# EC_isolated_SMD.net
KiCad netlist of a schematic drawn in EAGLE
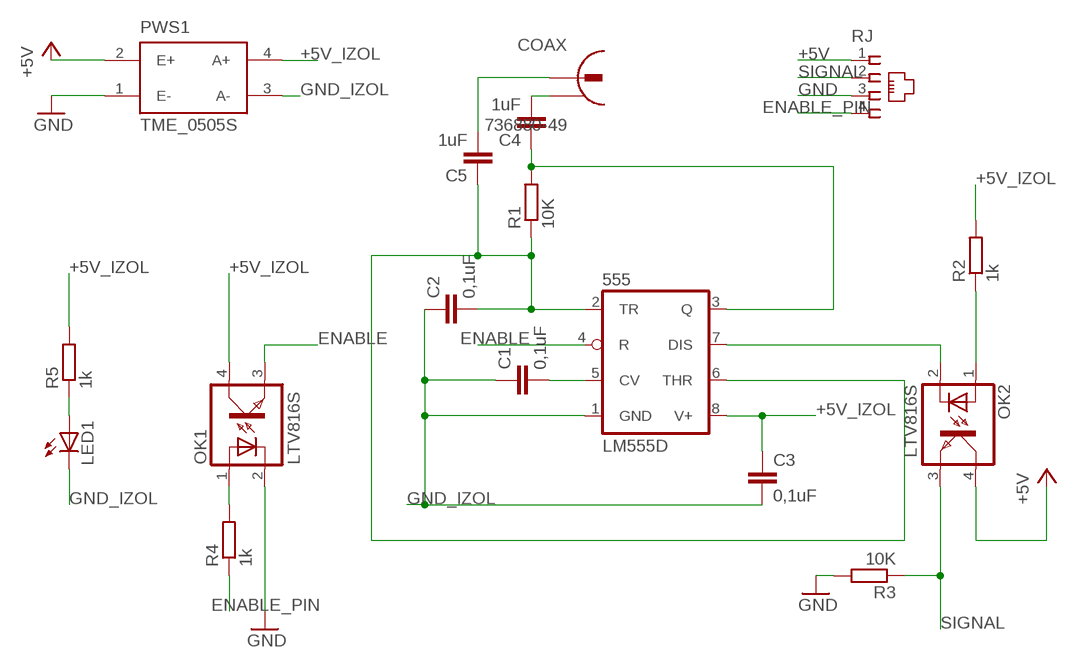
[diagram p0: schematic, sheet 1]

(export (version "E")
  (design (tool "Eeschema 10.0.6"))
  (components
    (comp (ref "555")
      (value "LM555D")
      (footprint "eagle-import:SO08")
      (libsource (lib "eagle-import") (part "555DLM"))
    )
    (comp (ref "C1")
      (value "0,1uF")
      (footprint "eagle-import:C1206")
      (libsource (lib "eagle-import") (part "C-EUC1206"))
    )
    (comp (ref "C2")
      (value "0,1uF")
      (footprint "eagle-import:C1206")
      (libsource (lib "eagle-import") (part "C-EUC1206"))
    )
    (comp (ref "C3")
      (value "0,1uF")
      (footprint "eagle-import:C1206")
      (libsource (lib "eagle-import") (part "C-EUC1206"))
    )
    (comp (ref "C4")
      (value "1uF")
      (footprint "eagle-import:C1206")
      (libsource (lib "eagle-import") (part "C-EUC1206"))
    )
    (comp (ref "C5")
      (value "1uF")
      (footprint "eagle-import:C1206")
      (libsource (lib "eagle-import") (part "C-EUC1206"))
    )
    (comp (ref "COAX")
      (value "736880-49")
      (footprint "eagle-import:736880-49")
      (libsource (lib "eagle-import") (part "736880-49"))
    )
    (comp (ref "LED1")
      (value "LEDLZR181")
      (footprint "eagle-import:LZR181")
      (libsource (lib "eagle-import") (part "LEDLZR181"))
    )
    (comp (ref "OK1")
      (value "LTV816S")
      (footprint "eagle-import:SMD4")
      (fields (field (name "OC_FARNELL") "unknown") (field (name "OC_NEWARK") "unknown"))
      (libsource (lib "eagle-import") (part "LTV816S"))
    )
    (comp (ref "OK2")
      (value "LTV816S")
      (footprint "eagle-import:SMD4")
      (fields (field (name "OC_FARNELL") "unknown") (field (name "OC_NEWARK") "unknown"))
      (libsource (lib "eagle-import") (part "LTV816S"))
    )
    (comp (ref "PWS1")
      (value "TME_0505S")
      (footprint "eagle-import:TMEXXXXS")
      (fields (field (name "MPN") "TME 0505S"))
      (libsource (lib "eagle-import") (part "TME_S0505"))
    )
    (comp (ref "R1")
      (value "10K")
      (footprint "eagle-import:R1206W")
      (libsource (lib "eagle-import") (part "R-EU_R1206W"))
    )
    (comp (ref "R2")
      (value "1k")
      (footprint "eagle-import:R1206W")
      (libsource (lib "eagle-import") (part "R-EU_R1206W"))
    )
    (comp (ref "R3")
      (value "10K")
      (footprint "eagle-import:R0805W")
      (libsource (lib "eagle-import") (part "R-EU_R0805W"))
    )
    (comp (ref "R4")
      (value "1k")
      (footprint "eagle-import:R1206W")
      (libsource (lib "eagle-import") (part "R-EU_R1206W"))
    )
    (comp (ref "R5")
      (value "1k")
      (footprint "eagle-import:R0805W")
      (libsource (lib "eagle-import") (part "R-EU_R0805W"))
    )
    (comp (ref "RJ")
      (value "14867")
      (footprint "eagle-import:14867")
      (libsource (lib "eagle-import") (part "14867"))
    )
  )
  (nets
    (net (code "1") (name "+5V") (class "Default")
      (node (ref "OK2") (pin "4") (pinfunction "COL_4") (pintype "passive"))
      (node (ref "PWS1") (pin "2") (pinfunction "E+_2") (pintype "input"))
      (node (ref "RJ") (pin "1") (pinfunction "1_1") (pintype "passive"))
    )
    (net (code "2") (name "/+5V_IZOL") (class "Default")
      (node (ref "555") (pin "8") (pinfunction "V+_8") (pintype "power_in"))
      (node (ref "C3") (pin "1") (pinfunction "1_1") (pintype "passive"))
      (node (ref "OK1") (pin "4") (pinfunction "COL_4") (pintype "passive"))
      (node (ref "PWS1") (pin "4") (pinfunction "A+_4") (pintype "output"))
      (node (ref "R2") (pin "2") (pinfunction "2_2") (pintype "passive"))
      (node (ref "R5") (pin "2") (pinfunction "2_2") (pintype "passive"))
    )
    (net (code "3") (name "/ENABLE") (class "Default")
      (node (ref "555") (pin "4") (pinfunction "R_4") (pintype "input"))
      (node (ref "OK1") (pin "3") (pinfunction "EMIT_3") (pintype "passive"))
    )
    (net (code "4") (name "/ENABLE_PIN") (class "Default")
      (node (ref "R4") (pin "1") (pinfunction "1_1") (pintype "passive"))
      (node (ref "RJ") (pin "4") (pinfunction "4_4") (pintype "passive"))
    )
    (net (code "5") (name "/GND_IZOL") (class "Default")
      (node (ref "555") (pin "1") (pinfunction "GND_1") (pintype "power_in"))
      (node (ref "C1") (pin "1") (pinfunction "1_1") (pintype "passive"))
      (node (ref "C2") (pin "1") (pinfunction "1_1") (pintype "passive"))
      (node (ref "C3") (pin "2") (pinfunction "2_2") (pintype "passive"))
      (node (ref "LED1") (pin "K") (pinfunction "C_K") (pintype "passive"))
      (node (ref "PWS1") (pin "3") (pinfunction "A-_3") (pintype "output"))
    )
    (net (code "6") (name "/SIGNAL") (class "Default")
      (node (ref "OK2") (pin "3") (pinfunction "EMIT_3") (pintype "passive"))
      (node (ref "R3") (pin "1") (pinfunction "1_1") (pintype "passive"))
      (node (ref "RJ") (pin "2") (pinfunction "2_2") (pintype "passive"))
    )
    (net (code "7") (name "GND") (class "Default")
      (node (ref "OK1") (pin "2") (pinfunction "C_2") (pintype "passive"))
      (node (ref "PWS1") (pin "1") (pinfunction "E-_1") (pintype "input"))
      (node (ref "R3") (pin "2") (pinfunction "2_2") (pintype "passive"))
      (node (ref "RJ") (pin "3") (pinfunction "3_3") (pintype "passive"))
    )
    (net (code "8") (name "Net-(555-CV)") (class "Default")
      (node (ref "555") (pin "5") (pinfunction "CV_5") (pintype "input"))
      (node (ref "C1") (pin "2") (pinfunction "2_2") (pintype "passive"))
    )
    (net (code "9") (name "Net-(555-DIS)") (class "Default")
      (node (ref "555") (pin "7") (pinfunction "DIS_7") (pintype "input"))
      (node (ref "OK2") (pin "2") (pinfunction "C_2") (pintype "passive"))
    )
    (net (code "10") (name "Net-(555-Q)") (class "Default")
      (node (ref "555") (pin "3") (pinfunction "Q_3") (pintype "output"))
      (node (ref "C4") (pin "1") (pinfunction "1_1") (pintype "passive"))
      (node (ref "R1") (pin "2") (pinfunction "2_2") (pintype "passive"))
    )
    (net (code "11") (name "Net-(555-THR)") (class "Default")
      (node (ref "555") (pin "2") (pinfunction "TR_2") (pintype "input"))
      (node (ref "555") (pin "6") (pinfunction "THR_6") (pintype "input"))
      (node (ref "C2") (pin "2") (pinfunction "2_2") (pintype "passive"))
      (node (ref "C5") (pin "1") (pinfunction "1_1") (pintype "passive"))
      (node (ref "R1") (pin "1") (pinfunction "1_1") (pintype "passive"))
    )
    (net (code "12") (name "Net-(C4-Pad2)") (class "Default")
      (node (ref "C4") (pin "2") (pinfunction "2_2") (pintype "passive"))
      (node (ref "COAX") (pin "2") (pinfunction "2_2") (pintype "passive"))
    )
    (net (code "13") (name "Net-(C5-Pad2)") (class "Default")
      (node (ref "C5") (pin "2") (pinfunction "2_2") (pintype "passive"))
      (node (ref "COAX") (pin "1") (pinfunction "1_1") (pintype "passive"))
    )
    (net (code "14") (name "Net-(LED1-PadA)") (class "Default")
      (node (ref "LED1") (pin "A") (pinfunction "A_A") (pintype "passive"))
      (node (ref "R5") (pin "1") (pinfunction "1_1") (pintype "passive"))
    )
    (net (code "15") (name "Net-(OK1-A)") (class "Default")
      (node (ref "OK1") (pin "1") (pinfunction "A_1") (pintype "passive"))
      (node (ref "R4") (pin "2") (pinfunction "2_2") (pintype "passive"))
    )
    (net (code "16") (name "Net-(OK2-A)") (class "Default")
      (node (ref "OK2") (pin "1") (pinfunction "A_1") (pintype "passive"))
      (node (ref "R2") (pin "1") (pinfunction "1_1") (pintype "passive"))
    )
    (net (code "17") (name "unconnected-(COAX-2-Pad2@2)") (class "Default")
      (node (ref "COAX") (pin "2@2") (pinfunction "2_2@2") (pintype "passive"))
    )
  )
)
